# RAMPSXB.net
KiCad netlist of a schematic drawn in EAGLE
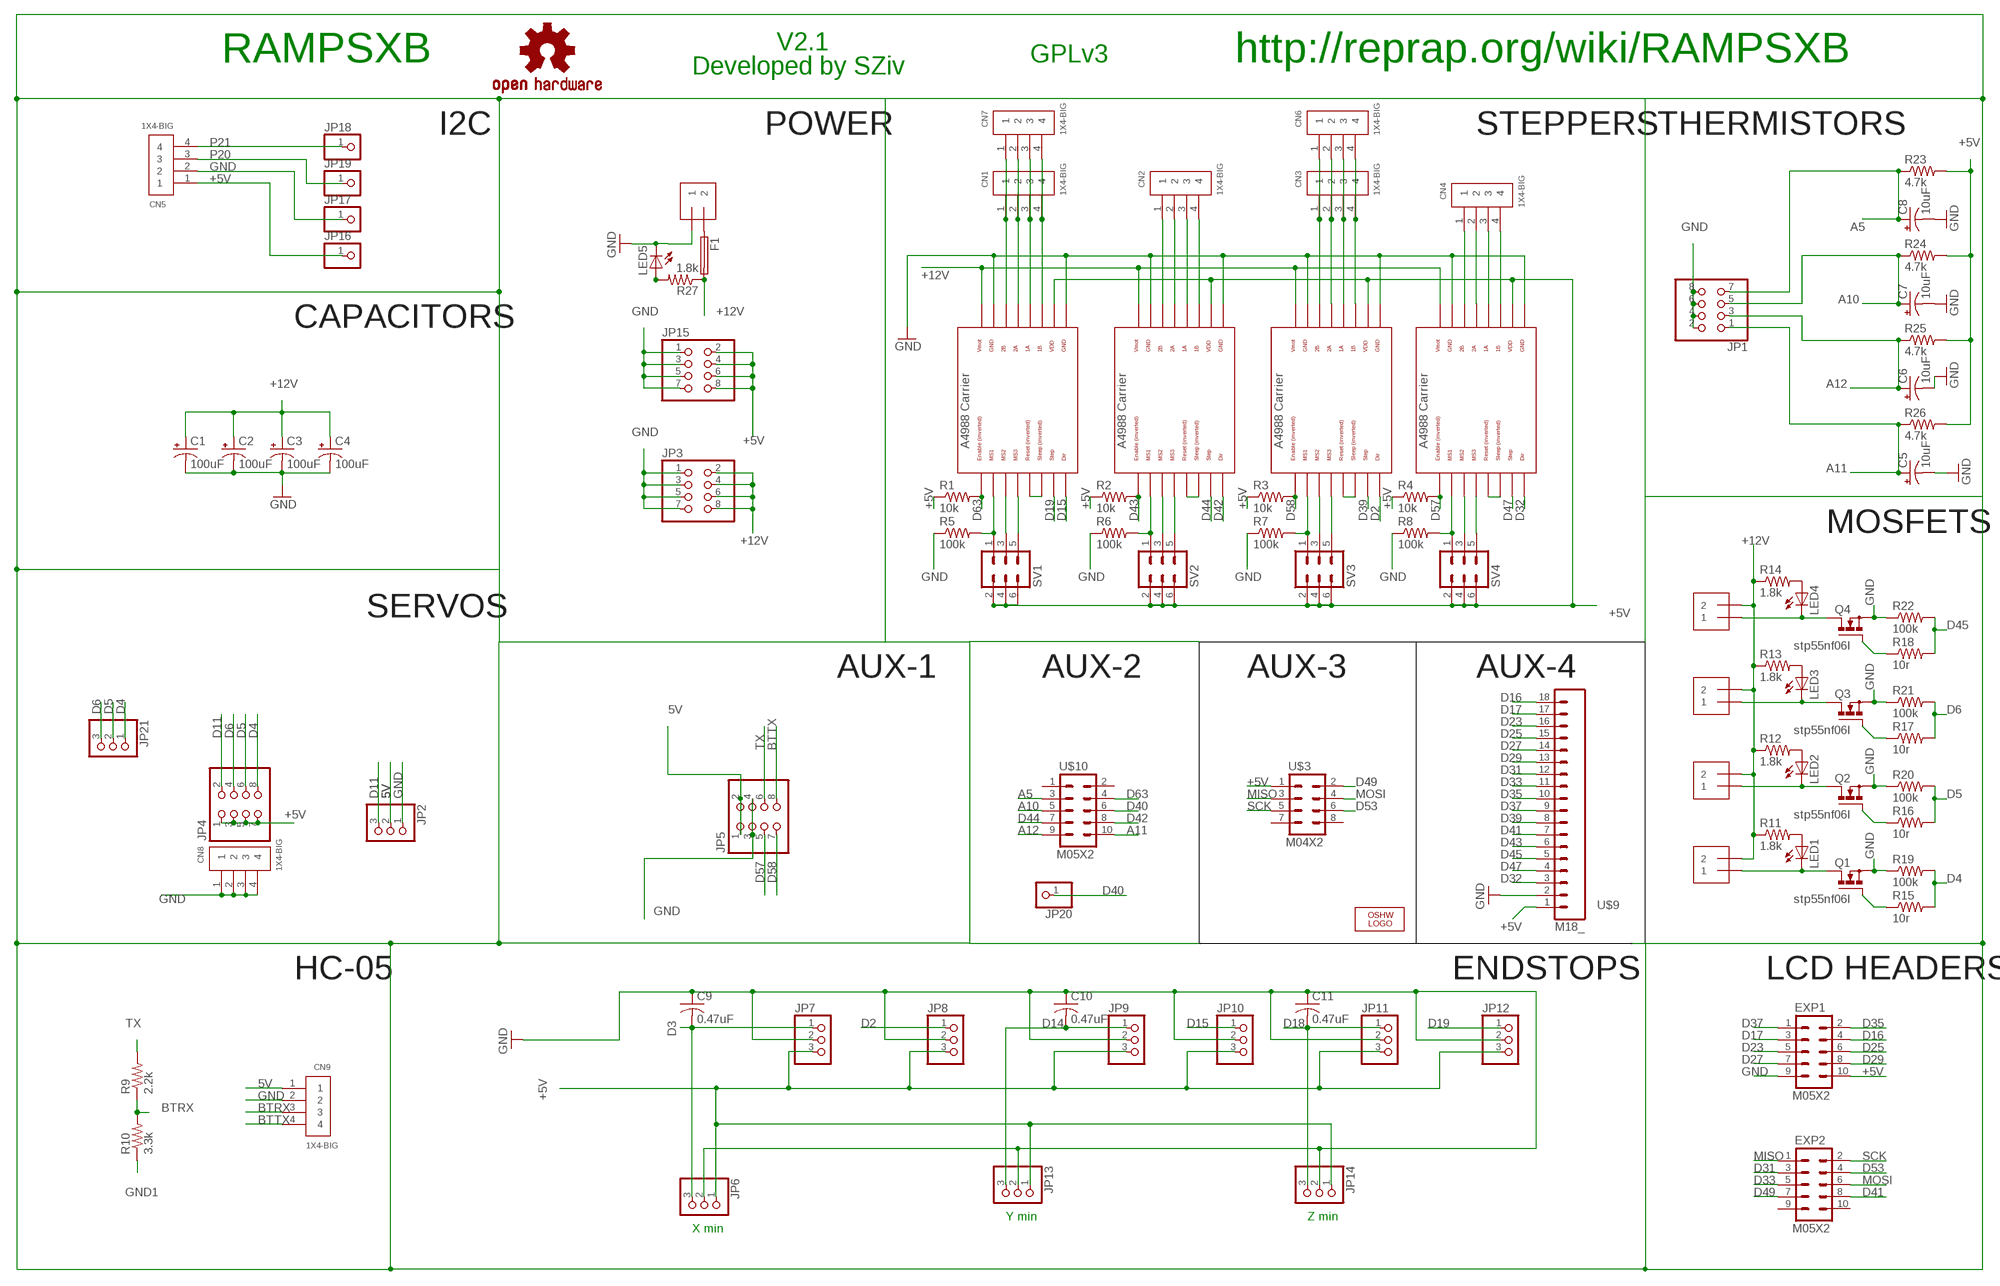
[diagram p0: schematic, sheet 1]

(export (version "E")
  (design (tool "Eeschema 10.0.6"))
  (components
    (comp (ref "C1")
      (value "100uF")
      (footprint "eagle-import:153CLV-0605")
      (libsource (lib "eagle-import") (part "CPOL-US153CLV-0605"))
    )
    (comp (ref "C2")
      (value "100uF")
      (footprint "eagle-import:153CLV-0605")
      (libsource (lib "eagle-import") (part "CPOL-US153CLV-0605"))
    )
    (comp (ref "C3")
      (value "100uF")
      (footprint "eagle-import:153CLV-0605")
      (libsource (lib "eagle-import") (part "CPOL-US153CLV-0605"))
    )
    (comp (ref "C4")
      (value "100uF")
      (footprint "eagle-import:153CLV-0605")
      (libsource (lib "eagle-import") (part "CPOL-US153CLV-0605"))
    )
    (comp (ref "C5")
      (value "10uF")
      (footprint "eagle-import:153CLV-0405")
      (libsource (lib "eagle-import") (part "CPOL-US153CLV-0405"))
    )
    (comp (ref "C6")
      (value "10uF")
      (footprint "eagle-import:153CLV-0405")
      (libsource (lib "eagle-import") (part "CPOL-US153CLV-0405"))
    )
    (comp (ref "C7")
      (value "10uF")
      (footprint "eagle-import:153CLV-0405")
      (libsource (lib "eagle-import") (part "CPOL-US153CLV-0405"))
    )
    (comp (ref "C8")
      (value "10uF")
      (footprint "eagle-import:153CLV-0405")
      (libsource (lib "eagle-import") (part "CPOL-US153CLV-0405"))
    )
    (comp (ref "C9")
      (value "0.47uF")
      (footprint "eagle-import:C0805")
      (libsource (lib "eagle-import") (part "C-USC0805"))
    )
    (comp (ref "C10")
      (value "0.47uF")
      (footprint "eagle-import:C0805")
      (libsource (lib "eagle-import") (part "C-USC0805"))
    )
    (comp (ref "C11")
      (value "0.47uF")
      (footprint "eagle-import:C0805")
      (libsource (lib "eagle-import") (part "C-USC0805"))
    )
    (comp (ref "CN1")
      (value "1X4-BIG")
      (footprint "eagle-import:1X04-BIG")
      (libsource (lib "eagle-import") (part "1X4-BIG"))
    )
    (comp (ref "CN2")
      (value "1X4-BIG")
      (footprint "eagle-import:1X04-BIG")
      (libsource (lib "eagle-import") (part "1X4-BIG"))
    )
    (comp (ref "CN3")
      (value "1X4-BIG")
      (footprint "eagle-import:1X04-BIG")
      (libsource (lib "eagle-import") (part "1X4-BIG"))
    )
    (comp (ref "CN4")
      (value "1X4-BIG")
      (footprint "eagle-import:1X04-BIG")
      (libsource (lib "eagle-import") (part "1X4-BIG"))
    )
    (comp (ref "CN5")
      (value "1X4-BIG")
      (footprint "eagle-import:1X04-BIG")
      (libsource (lib "eagle-import") (part "1X4-BIG"))
    )
    (comp (ref "CN6")
      (value "1X4-BIG")
      (footprint "eagle-import:1X04-BIG")
      (libsource (lib "eagle-import") (part "1X4-BIG"))
    )
    (comp (ref "CN7")
      (value "1X4-BIG")
      (footprint "eagle-import:1X04-BIG")
      (libsource (lib "eagle-import") (part "1X4-BIG"))
    )
    (comp (ref "CN8")
      (value "1X4-BIG")
      (footprint "eagle-import:1X04-BIG")
      (libsource (lib "eagle-import") (part "1X4-BIG"))
    )
    (comp (ref "CN9")
      (value "1X4-BIG")
      (footprint "eagle-import:1X04-BIG")
      (libsource (lib "eagle-import") (part "1X4-BIG"))
    )
    (comp (ref "EXP1")
      (value "M05X2")
      (footprint "eagle-import:2X5")
      (libsource (lib "eagle-import") (part "M05X2"))
    )
    (comp (ref "EXP2")
      (value "M05X2")
      (footprint "eagle-import:2X5")
      (libsource (lib "eagle-import") (part "M05X2"))
    )
    (comp (ref "F1")
      (value "PTCFUSE")
      (footprint "eagle-import:LITTLEFUSE")
      (libsource (lib "eagle-import") (part "PTCFUSE"))
    )
    (comp (ref "J1")
      (value "1X2-3.5MM")
      (footprint "eagle-import:1X2-3.5MM")
      (libsource (lib "eagle-import") (part "1X2-3.5MM"))
    )
    (comp (ref "J2")
      (value "1X2-3.5MM")
      (footprint "eagle-import:1X2-3.5MM")
      (libsource (lib "eagle-import") (part "1X2-3.5MM"))
    )
    (comp (ref "J3")
      (value "1X2-3.5MM")
      (footprint "eagle-import:1X2-3.5MM")
      (libsource (lib "eagle-import") (part "1X2-3.5MM"))
    )
    (comp (ref "J4")
      (value "1X2-3.5MM")
      (footprint "eagle-import:1X2-3.5MM")
      (libsource (lib "eagle-import") (part "1X2-3.5MM"))
    )
    (comp (ref "J5")
      (value "1X2-3.5MM")
      (footprint "eagle-import:1X2-3.5MM")
      (libsource (lib "eagle-import") (part "1X2-3.5MM"))
    )
    (comp (ref "JP1")
      (value "PINHD-2X4")
      (footprint "eagle-import:2X04")
      (libsource (lib "eagle-import") (part "PINHD-2X4"))
    )
    (comp (ref "JP2")
      (value "PINHD-1X3")
      (footprint "eagle-import:1X03")
      (libsource (lib "eagle-import") (part "PINHD-1X3"))
    )
    (comp (ref "JP3")
      (value "PINHD-2X4")
      (footprint "eagle-import:2X04")
      (libsource (lib "eagle-import") (part "PINHD-2X4"))
    )
    (comp (ref "JP4")
      (value "PINHD-2X4")
      (footprint "eagle-import:2X04")
      (libsource (lib "eagle-import") (part "PINHD-2X4"))
    )
    (comp (ref "JP5")
      (value "PINHD-2X4")
      (footprint "eagle-import:2X04")
      (libsource (lib "eagle-import") (part "PINHD-2X4"))
    )
    (comp (ref "JP6")
      (value "PINHD-1X3")
      (footprint "eagle-import:1X03")
      (libsource (lib "eagle-import") (part "PINHD-1X3"))
    )
    (comp (ref "JP7")
      (value "PINHD-1X3")
      (footprint "eagle-import:1X03")
      (libsource (lib "eagle-import") (part "PINHD-1X3"))
    )
    (comp (ref "JP8")
      (value "PINHD-1X3")
      (footprint "eagle-import:1X03")
      (libsource (lib "eagle-import") (part "PINHD-1X3"))
    )
    (comp (ref "JP9")
      (value "PINHD-1X3")
      (footprint "eagle-import:1X03")
      (libsource (lib "eagle-import") (part "PINHD-1X3"))
    )
    (comp (ref "JP10")
      (value "PINHD-1X3")
      (footprint "eagle-import:1X03")
      (libsource (lib "eagle-import") (part "PINHD-1X3"))
    )
    (comp (ref "JP11")
      (value "PINHD-1X3")
      (footprint "eagle-import:1X03")
      (libsource (lib "eagle-import") (part "PINHD-1X3"))
    )
    (comp (ref "JP12")
      (value "PINHD-1X3")
      (footprint "eagle-import:1X03")
      (libsource (lib "eagle-import") (part "PINHD-1X3"))
    )
    (comp (ref "JP13")
      (value "PINHD-1X3")
      (footprint "eagle-import:1X03")
      (libsource (lib "eagle-import") (part "PINHD-1X3"))
    )
    (comp (ref "JP14")
      (value "PINHD-1X3")
      (footprint "eagle-import:1X03")
      (libsource (lib "eagle-import") (part "PINHD-1X3"))
    )
    (comp (ref "JP15")
      (value "PINHD-2X4")
      (footprint "eagle-import:2X04")
      (libsource (lib "eagle-import") (part "PINHD-2X4"))
    )
    (comp (ref "JP16")
      (value "PINHD-1X1")
      (footprint "eagle-import:1X01")
      (libsource (lib "eagle-import") (part "PINHD-1X1"))
    )
    (comp (ref "JP17")
      (value "PINHD-1X1")
      (footprint "eagle-import:1X01")
      (libsource (lib "eagle-import") (part "PINHD-1X1"))
    )
    (comp (ref "JP18")
      (value "PINHD-1X1")
      (footprint "eagle-import:1X01")
      (libsource (lib "eagle-import") (part "PINHD-1X1"))
    )
    (comp (ref "JP19")
      (value "PINHD-1X1")
      (footprint "eagle-import:1X01")
      (libsource (lib "eagle-import") (part "PINHD-1X1"))
    )
    (comp (ref "JP20")
      (value "PINHD-1X1")
      (footprint "eagle-import:1X01")
      (libsource (lib "eagle-import") (part "PINHD-1X1"))
    )
    (comp (ref "JP21")
      (value "PINHD-1X3")
      (footprint "eagle-import:1X03")
      (libsource (lib "eagle-import") (part "PINHD-1X3"))
    )
    (comp (ref "LED1")
      (value "LEDCHIPLED_0805")
      (footprint "eagle-import:CHIPLED_0805")
      (libsource (lib "eagle-import") (part "LEDCHIPLED_0805"))
    )
    (comp (ref "LED2")
      (value "LEDCHIPLED_0805")
      (footprint "eagle-import:CHIPLED_0805")
      (libsource (lib "eagle-import") (part "LEDCHIPLED_0805"))
    )
    (comp (ref "LED3")
      (value "LEDCHIPLED_0805")
      (footprint "eagle-import:CHIPLED_0805")
      (libsource (lib "eagle-import") (part "LEDCHIPLED_0805"))
    )
    (comp (ref "LED4")
      (value "LEDCHIPLED_0805")
      (footprint "eagle-import:CHIPLED_0805")
      (libsource (lib "eagle-import") (part "LEDCHIPLED_0805"))
    )
    (comp (ref "LED5")
      (value "LEDCHIPLED_0805")
      (footprint "eagle-import:CHIPLED_0805")
      (libsource (lib "eagle-import") (part "LEDCHIPLED_0805"))
    )
    (comp (ref "LOGO1")
      (value "OSHW_LOGO_6MILX0100-NT")
      (footprint "eagle-import:OSHW_6X100_NOTEXT")
      (libsource (lib "eagle-import") (part "OSHW_LOGO_6MILX0100-NT"))
    )
    (comp (ref "LOGO2")
      (value "OSHW-LOGOL")
      (footprint "eagle-import:OSHW-LOGO-L")
      (libsource (lib "eagle-import") (part "OSHW-LOGOL"))
    )
    (comp (ref "Q1")
      (value "IRF512")
      (footprint "eagle-import:TO220BV")
      (libsource (lib "eagle-import") (part "IRF512"))
    )
    (comp (ref "Q2")
      (value "IRF512")
      (footprint "eagle-import:TO220BV")
      (libsource (lib "eagle-import") (part "IRF512"))
    )
    (comp (ref "Q3")
      (value "IRF512")
      (footprint "eagle-import:TO220BV")
      (libsource (lib "eagle-import") (part "IRF512"))
    )
    (comp (ref "Q4")
      (value "IRF512")
      (footprint "eagle-import:TO220BV")
      (libsource (lib "eagle-import") (part "IRF512"))
    )
    (comp (ref "R1")
      (value "10k")
      (footprint "eagle-import:M0805")
      (libsource (lib "eagle-import") (part "R-US_M0805"))
    )
    (comp (ref "R2")
      (value "10k")
      (footprint "eagle-import:M0805")
      (libsource (lib "eagle-import") (part "R-US_M0805"))
    )
    (comp (ref "R3")
      (value "10k")
      (footprint "eagle-import:M0805")
      (libsource (lib "eagle-import") (part "R-US_M0805"))
    )
    (comp (ref "R4")
      (value "10k")
      (footprint "eagle-import:M0805")
      (libsource (lib "eagle-import") (part "R-US_M0805"))
    )
    (comp (ref "R5")
      (value "100k")
      (footprint "eagle-import:M0805")
      (libsource (lib "eagle-import") (part "R-US_M0805"))
    )
    (comp (ref "R6")
      (value "100k")
      (footprint "eagle-import:M0805")
      (libsource (lib "eagle-import") (part "R-US_M0805"))
    )
    (comp (ref "R7")
      (value "100k")
      (footprint "eagle-import:M0805")
      (libsource (lib "eagle-import") (part "R-US_M0805"))
    )
    (comp (ref "R8")
      (value "100k")
      (footprint "eagle-import:M0805")
      (libsource (lib "eagle-import") (part "R-US_M0805"))
    )
    (comp (ref "R9")
      (value "2.2k")
      (footprint "eagle-import:M0805")
      (libsource (lib "eagle-import") (part "R-US_M0805"))
    )
    (comp (ref "R10")
      (value "3.3k")
      (footprint "eagle-import:M0805")
      (libsource (lib "eagle-import") (part "R-US_M0805"))
    )
    (comp (ref "R11")
      (value "1.8k")
      (footprint "eagle-import:M0805")
      (libsource (lib "eagle-import") (part "R-US_M0805"))
    )
    (comp (ref "R12")
      (value "1.8k")
      (footprint "eagle-import:M0805")
      (libsource (lib "eagle-import") (part "R-US_M0805"))
    )
    (comp (ref "R13")
      (value "1.8k")
      (footprint "eagle-import:M0805")
      (libsource (lib "eagle-import") (part "R-US_M0805"))
    )
    (comp (ref "R14")
      (value "1.8k")
      (footprint "eagle-import:M0805")
      (libsource (lib "eagle-import") (part "R-US_M0805"))
    )
    (comp (ref "R15")
      (value "10r")
      (footprint "eagle-import:M0805")
      (libsource (lib "eagle-import") (part "R-US_M0805"))
    )
    (comp (ref "R16")
      (value "10r")
      (footprint "eagle-import:M0805")
      (libsource (lib "eagle-import") (part "R-US_M0805"))
    )
    (comp (ref "R17")
      (value "10r")
      (footprint "eagle-import:M0805")
      (libsource (lib "eagle-import") (part "R-US_M0805"))
    )
    (comp (ref "R18")
      (value "10r")
      (footprint "eagle-import:M0805")
      (libsource (lib "eagle-import") (part "R-US_M0805"))
    )
    (comp (ref "R19")
      (value "100k")
      (footprint "eagle-import:M0805")
      (libsource (lib "eagle-import") (part "R-US_M0805"))
    )
    (comp (ref "R20")
      (value "100k")
      (footprint "eagle-import:M0805")
      (libsource (lib "eagle-import") (part "R-US_M0805"))
    )
    (comp (ref "R21")
      (value "100k")
      (footprint "eagle-import:M0805")
      (libsource (lib "eagle-import") (part "R-US_M0805"))
    )
    (comp (ref "R22")
      (value "100k")
      (footprint "eagle-import:M0805")
      (libsource (lib "eagle-import") (part "R-US_M0805"))
    )
    (comp (ref "R23")
      (value "4.7k")
      (footprint "eagle-import:R0805")
      (libsource (lib "eagle-import") (part "R-US_R0805"))
    )
    (comp (ref "R24")
      (value "4.7k")
      (footprint "eagle-import:R0805")
      (libsource (lib "eagle-import") (part "R-US_R0805"))
    )
    (comp (ref "R25")
      (value "4.7k")
      (footprint "eagle-import:R0805")
      (libsource (lib "eagle-import") (part "R-US_R0805"))
    )
    (comp (ref "R26")
      (value "4.7k")
      (footprint "eagle-import:R0805")
      (libsource (lib "eagle-import") (part "R-US_R0805"))
    )
    (comp (ref "R27")
      (value "1.8k")
      (footprint "eagle-import:M0805")
      (libsource (lib "eagle-import") (part "R-US_M0805"))
    )
    (comp (ref "SV1")
      (value "MA03-2")
      (footprint "eagle-import:MA03-2")
      (libsource (lib "eagle-import") (part "MA03-2"))
    )
    (comp (ref "SV2")
      (value "MA03-2")
      (footprint "eagle-import:MA03-2")
      (libsource (lib "eagle-import") (part "MA03-2"))
    )
    (comp (ref "SV3")
      (value "MA03-2")
      (footprint "eagle-import:MA03-2")
      (libsource (lib "eagle-import") (part "MA03-2"))
    )
    (comp (ref "SV4")
      (value "MA03-2")
      (footprint "eagle-import:MA03-2")
      (libsource (lib "eagle-import") (part "MA03-2"))
    )
    (comp (ref "U$1")
      (value "POLOLU_A4983CARRIER")
      (footprint "eagle-import:A4988BREAKOUT")
      (libsource (lib "eagle-import") (part "POLOLU_A4983CARRIER"))
    )
    (comp (ref "U$2")
      (value "POLOLU_A4983CARRIER")
      (footprint "eagle-import:A4988BREAKOUT")
      (libsource (lib "eagle-import") (part "POLOLU_A4983CARRIER"))
    )
    (comp (ref "U$3")
      (value "M04X2")
      (footprint "eagle-import:2X4")
      (libsource (lib "eagle-import") (part "M04X2"))
    )
    (comp (ref "U$4")
      (value "POLOLU_A4983CARRIER")
      (footprint "eagle-import:A4988BREAKOUT")
      (libsource (lib "eagle-import") (part "POLOLU_A4983CARRIER"))
    )
    (comp (ref "U$5")
      (value "POLOLU_A4983CARRIER")
      (footprint "eagle-import:A4988BREAKOUT")
      (libsource (lib "eagle-import") (part "POLOLU_A4983CARRIER"))
    )
    (comp (ref "U$9")
      (value "M18_")
      (footprint "eagle-import:1X18")
      (libsource (lib "eagle-import") (part "M18_"))
    )
    (comp (ref "U$10")
      (value "M05X2")
      (footprint "eagle-import:2X5")
      (libsource (lib "eagle-import") (part "M05X2"))
    )
  )
  (nets
    (net (code "1") (name "/+5V") (class "Default")
      (node (ref "CN5") (pin "1") (pinfunction "1_1") (pintype "bidirectional"))
      (node (ref "EXP1") (pin "10") (pinfunction "10_10") (pintype "passive"))
      (node (ref "JP10") (pin "3") (pinfunction "3_3") (pintype "passive"))
      (node (ref "JP11") (pin "3") (pinfunction "3_3") (pintype "passive"))
      (node (ref "JP12") (pin "3") (pinfunction "3_3") (pintype "passive"))
      (node (ref "JP13") (pin "1") (pinfunction "1_1") (pintype "passive"))
      (node (ref "JP14") (pin "1") (pinfunction "1_1") (pintype "passive"))
      (node (ref "JP15") (pin "2") (pinfunction "2_2") (pintype "passive"))
      (node (ref "JP15") (pin "4") (pinfunction "4_4") (pintype "passive"))
      (node (ref "JP15") (pin "6") (pinfunction "6_6") (pintype "passive"))
      (node (ref "JP15") (pin "8") (pinfunction "8_8") (pintype "passive"))
      (node (ref "JP16") (pin "1") (pinfunction "1_1") (pintype "passive"))
      (node (ref "JP4") (pin "1") (pinfunction "1_1") (pintype "passive"))
      (node (ref "JP4") (pin "3") (pinfunction "3_3") (pintype "passive"))
      (node (ref "JP4") (pin "5") (pinfunction "5_5") (pintype "passive"))
      (node (ref "JP4") (pin "7") (pinfunction "7_7") (pintype "passive"))
      (node (ref "JP6") (pin "1") (pinfunction "1_1") (pintype "passive"))
      (node (ref "JP7") (pin "3") (pinfunction "3_3") (pintype "passive"))
      (node (ref "JP8") (pin "3") (pinfunction "3_3") (pintype "passive"))
      (node (ref "JP9") (pin "3") (pinfunction "3_3") (pintype "passive"))
      (node (ref "R1") (pin "1") (pinfunction "1_1") (pintype "passive"))
      (node (ref "R2") (pin "1") (pinfunction "1_1") (pintype "passive"))
      (node (ref "R23") (pin "2") (pinfunction "2_2") (pintype "passive"))
      (node (ref "R24") (pin "2") (pinfunction "2_2") (pintype "passive"))
      (node (ref "R25") (pin "2") (pinfunction "2_2") (pintype "passive"))
      (node (ref "R26") (pin "2") (pinfunction "2_2") (pintype "passive"))
      (node (ref "R3") (pin "1") (pinfunction "1_1") (pintype "passive"))
      (node (ref "R4") (pin "1") (pinfunction "1_1") (pintype "passive"))
      (node (ref "SV1") (pin "2") (pinfunction "2_2") (pintype "passive"))
      (node (ref "SV1") (pin "4") (pinfunction "4_4") (pintype "passive"))
      (node (ref "SV1") (pin "6") (pinfunction "6_6") (pintype "passive"))
      (node (ref "SV2") (pin "2") (pinfunction "2_2") (pintype "passive"))
      (node (ref "SV2") (pin "4") (pinfunction "4_4") (pintype "passive"))
      (node (ref "SV2") (pin "6") (pinfunction "6_6") (pintype "passive"))
      (node (ref "SV3") (pin "2") (pinfunction "2_2") (pintype "passive"))
      (node (ref "SV3") (pin "4") (pinfunction "4_4") (pintype "passive"))
      (node (ref "SV3") (pin "6") (pinfunction "6_6") (pintype "passive"))
      (node (ref "SV4") (pin "2") (pinfunction "2_2") (pintype "passive"))
      (node (ref "SV4") (pin "4") (pinfunction "4_4") (pintype "passive"))
      (node (ref "SV4") (pin "6") (pinfunction "6_6") (pintype "passive"))
      (node (ref "U$1") (pin "VDD") (pinfunction "VDD_VDD") (pintype "power_in"))
      (node (ref "U$2") (pin "VDD") (pinfunction "VDD_VDD") (pintype "power_in"))
      (node (ref "U$3") (pin "1") (pinfunction "1_1") (pintype "passive"))
      (node (ref "U$4") (pin "VDD") (pinfunction "VDD_VDD") (pintype "power_in"))
      (node (ref "U$5") (pin "VDD") (pinfunction "VDD_VDD") (pintype "power_in"))
      (node (ref "U$9") (pin "1") (pinfunction "1_1") (pintype "passive"))
    )
    (net (code "2") (name "/+12V") (class "Default")
      (node (ref "C1") (pin "+") (pinfunction "+_+") (pintype "passive"))
      (node (ref "C2") (pin "+") (pinfunction "+_+") (pintype "passive"))
      (node (ref "C3") (pin "+") (pinfunction "+_+") (pintype "passive"))
      (node (ref "C4") (pin "+") (pinfunction "+_+") (pintype "passive"))
      (node (ref "F1") (pin "2") (pinfunction "2_2") (pintype "passive"))
      (node (ref "J2") (pin "2") (pinfunction "2_2") (pintype "passive"))
      (node (ref "J3") (pin "2") (pinfunction "2_2") (pintype "passive"))
      (node (ref "J4") (pin "2") (pinfunction "2_2") (pintype "passive"))
      (node (ref "J5") (pin "2") (pinfunction "2_2") (pintype "passive"))
      (node (ref "JP3") (pin "2") (pinfunction "2_2") (pintype "passive"))
      (node (ref "JP3") (pin "4") (pinfunction "4_4") (pintype "passive"))
      (node (ref "JP3") (pin "6") (pinfunction "6_6") (pintype "passive"))
      (node (ref "JP3") (pin "8") (pinfunction "8_8") (pintype "passive"))
      (node (ref "R11") (pin "1") (pinfunction "1_1") (pintype "passive"))
      (node (ref "R12") (pin "1") (pinfunction "1_1") (pintype "passive"))
      (node (ref "R13") (pin "1") (pinfunction "1_1") (pintype "passive"))
      (node (ref "R14") (pin "1") (pinfunction "1_1") (pintype "passive"))
      (node (ref "R27") (pin "1") (pinfunction "1_1") (pintype "passive"))
      (node (ref "U$1") (pin "VMOT") (pinfunction "VMOT_VMOT") (pintype "power_in"))
      (node (ref "U$2") (pin "VMOT") (pinfunction "VMOT_VMOT") (pintype "power_in"))
      (node (ref "U$4") (pin "VMOT") (pinfunction "VMOT_VMOT") (pintype "power_in"))
      (node (ref "U$5") (pin "VMOT") (pinfunction "VMOT_VMOT") (pintype "power_in"))
    )
    (net (code "3") (name "/5V") (class "Default")
      (node (ref "CN9") (pin "1") (pinfunction "1_1") (pintype "bidirectional"))
      (node (ref "JP2") (pin "2") (pinfunction "2_2") (pintype "passive"))
      (node (ref "JP5") (pin "1") (pinfunction "1_1") (pintype "passive"))
      (node (ref "JP5") (pin "2") (pinfunction "2_2") (pintype "passive"))
    )
    (net (code "4") (name "/A5") (class "Default")
      (node (ref "C8") (pin "+") (pinfunction "+_+") (pintype "passive"))
      (node (ref "JP1") (pin "7") (pinfunction "7_7") (pintype "passive"))
      (node (ref "R23") (pin "1") (pinfunction "1_1") (pintype "passive"))
      (node (ref "U$10") (pin "3") (pinfunction "3_3") (pintype "passive"))
    )
    (net (code "5") (name "/A10") (class "Default")
      (node (ref "C7") (pin "+") (pinfunction "+_+") (pintype "passive"))
      (node (ref "JP1") (pin "5") (pinfunction "5_5") (pintype "passive"))
      (node (ref "R24") (pin "1") (pinfunction "1_1") (pintype "passive"))
      (node (ref "U$10") (pin "5") (pinfunction "5_5") (pintype "passive"))
    )
    (net (code "6") (name "/A11") (class "Default")
      (node (ref "C5") (pin "+") (pinfunction "+_+") (pintype "passive"))
      (node (ref "JP1") (pin "1") (pinfunction "1_1") (pintype "passive"))
      (node (ref "R26") (pin "1") (pinfunction "1_1") (pintype "passive"))
      (node (ref "U$10") (pin "10") (pinfunction "10_10") (pintype "passive"))
    )
    (net (code "7") (name "/A12") (class "Default")
      (node (ref "C6") (pin "+") (pinfunction "+_+") (pintype "passive"))
      (node (ref "JP1") (pin "3") (pinfunction "3_3") (pintype "passive"))
      (node (ref "R25") (pin "1") (pinfunction "1_1") (pintype "passive"))
      (node (ref "U$10") (pin "9") (pinfunction "9_9") (pintype "passive"))
    )
    (net (code "8") (name "/BTRX") (class "Default")
      (node (ref "CN9") (pin "3") (pinfunction "3_3") (pintype "bidirectional"))
      (node (ref "R10") (pin "2") (pinfunction "2_2") (pintype "passive"))
      (node (ref "R9") (pin "1") (pinfunction "1_1") (pintype "passive"))
    )
    (net (code "9") (name "/BTTX") (class "Default")
      (node (ref "CN9") (pin "4") (pinfunction "4_4") (pintype "bidirectional"))
      (node (ref "JP5") (pin "8") (pinfunction "8_8") (pintype "passive"))
    )
    (net (code "10") (name "/D2") (class "Default")
      (node (ref "JP8") (pin "1") (pinfunction "1_1") (pintype "passive"))
      (node (ref "U$4") (pin "DIR") (pinfunction "DIR_DIR") (pintype "input"))
    )
    (net (code "11") (name "/D3") (class "Default")
      (node (ref "C9") (pin "2") (pinfunction "2_2") (pintype "passive"))
      (node (ref "JP6") (pin "3") (pinfunction "3_3") (pintype "passive"))
      (node (ref "JP7") (pin "1") (pinfunction "1_1") (pintype "passive"))
    )
    (net (code "12") (name "/D4") (class "Default")
      (node (ref "JP21") (pin "1") (pinfunction "1_1") (pintype "passive"))
      (node (ref "JP4") (pin "8") (pinfunction "8_8") (pintype "passive"))
      (node (ref "R15") (pin "2") (pinfunction "2_2") (pintype "passive"))
      (node (ref "R19") (pin "2") (pinfunction "2_2") (pintype "passive"))
    )
    (net (code "13") (name "/D5") (class "Default")
      (node (ref "JP21") (pin "2") (pinfunction "2_2") (pintype "passive"))
      (node (ref "JP4") (pin "6") (pinfunction "6_6") (pintype "passive"))
      (node (ref "R16") (pin "2") (pinfunction "2_2") (pintype "passive"))
      (node (ref "R20") (pin "2") (pinfunction "2_2") (pintype "passive"))
    )
    (net (code "14") (name "/D6") (class "Default")
      (node (ref "JP21") (pin "3") (pinfunction "3_3") (pintype "passive"))
      (node (ref "JP4") (pin "4") (pinfunction "4_4") (pintype "passive"))
      (node (ref "R17") (pin "2") (pinfunction "2_2") (pintype "passive"))
      (node (ref "R21") (pin "2") (pinfunction "2_2") (pintype "passive"))
    )
    (net (code "15") (name "/D11") (class "Default")
      (node (ref "JP2") (pin "3") (pinfunction "3_3") (pintype "passive"))
      (node (ref "JP4") (pin "2") (pinfunction "2_2") (pintype "passive"))
    )
    (net (code "16") (name "/D14") (class "Default")
      (node (ref "C10") (pin "2") (pinfunction "2_2") (pintype "passive"))
      (node (ref "JP13") (pin "3") (pinfunction "3_3") (pintype "passive"))
      (node (ref "JP9") (pin "1") (pinfunction "1_1") (pintype "passive"))
    )
    (net (code "17") (name "/D15") (class "Default")
      (node (ref "JP10") (pin "1") (pinfunction "1_1") (pintype "passive"))
      (node (ref "U$1") (pin "DIR") (pinfunction "DIR_DIR") (pintype "input"))
    )
    (net (code "18") (name "/D16") (class "Default")
      (node (ref "EXP1") (pin "4") (pinfunction "4_4") (pintype "passive"))
      (node (ref "U$9") (pin "18") (pinfunction "18_18") (pintype "passive"))
    )
    (net (code "19") (name "/D17") (class "Default")
      (node (ref "EXP1") (pin "3") (pinfunction "3_3") (pintype "passive"))
      (node (ref "U$9") (pin "17") (pinfunction "17_17") (pintype "passive"))
    )
    (net (code "20") (name "/D18") (class "Default")
      (node (ref "C11") (pin "2") (pinfunction "2_2") (pintype "passive"))
      (node (ref "JP11") (pin "1") (pinfunction "1_1") (pintype "passive"))
      (node (ref "JP14") (pin "3") (pinfunction "3_3") (pintype "passive"))
    )
    (net (code "21") (name "/D19") (class "Default")
      (node (ref "JP12") (pin "1") (pinfunction "1_1") (pintype "passive"))
      (node (ref "U$1") (pin "STEP") (pinfunction "STEP_STEP") (pintype "input"))
    )
    (net (code "22") (name "/D23") (class "Default")
      (node (ref "EXP1") (pin "5") (pinfunction "5_5") (pintype "passive"))
      (node (ref "U$9") (pin "16") (pinfunction "16_16") (pintype "passive"))
    )
    (net (code "23") (name "/D25") (class "Default")
      (node (ref "EXP1") (pin "6") (pinfunction "6_6") (pintype "passive"))
      (node (ref "U$9") (pin "15") (pinfunction "15_15") (pintype "passive"))
    )
    (net (code "24") (name "/D27") (class "Default")
      (node (ref "EXP1") (pin "7") (pinfunction "7_7") (pintype "passive"))
      (node (ref "U$9") (pin "14") (pinfunction "14_14") (pintype "passive"))
    )
    (net (code "25") (name "/D29") (class "Default")
      (node (ref "EXP1") (pin "8") (pinfunction "8_8") (pintype "passive"))
      (node (ref "U$9") (pin "13") (pinfunction "13_13") (pintype "passive"))
    )
    (net (code "26") (name "/D31") (class "Default")
      (node (ref "EXP2") (pin "3") (pinfunction "3_3") (pintype "passive"))
      (node (ref "U$9") (pin "12") (pinfunction "12_12") (pintype "passive"))
    )
    (net (code "27") (name "/D32") (class "Default")
      (node (ref "U$5") (pin "DIR") (pinfunction "DIR_DIR") (pintype "input"))
      (node (ref "U$9") (pin "3") (pinfunction "3_3") (pintype "passive"))
    )
    (net (code "28") (name "/D33") (class "Default")
      (node (ref "EXP2") (pin "5") (pinfunction "5_5") (pintype "passive"))
      (node (ref "U$9") (pin "11") (pinfunction "11_11") (pintype "passive"))
    )
    (net (code "29") (name "/D35") (class "Default")
      (node (ref "EXP1") (pin "2") (pinfunction "2_2") (pintype "passive"))
      (node (ref "U$9") (pin "10") (pinfunction "10_10") (pintype "passive"))
    )
    (net (code "30") (name "/D37") (class "Default")
      (node (ref "EXP1") (pin "1") (pinfunction "1_1") (pintype "passive"))
      (node (ref "U$9") (pin "9") (pinfunction "9_9") (pintype "passive"))
    )
    (net (code "31") (name "/D39") (class "Default")
      (node (ref "U$4") (pin "STEP") (pinfunction "STEP_STEP") (pintype "input"))
      (node (ref "U$9") (pin "8") (pinfunction "8_8") (pintype "passive"))
    )
    (net (code "32") (name "/D40") (class "Default")
      (node (ref "JP20") (pin "1") (pinfunction "1_1") (pintype "passive"))
      (node (ref "U$10") (pin "6") (pinfunction "6_6") (pintype "passive"))
    )
    (net (code "33") (name "/D41") (class "Default")
      (node (ref "EXP2") (pin "8") (pinfunction "8_8") (pintype "passive"))
      (node (ref "U$9") (pin "7") (pinfunction "7_7") (pintype "passive"))
    )
    (net (code "34") (name "/D42") (class "Default")
      (node (ref "U$10") (pin "8") (pinfunction "8_8") (pintype "passive"))
      (node (ref "U$2") (pin "DIR") (pinfunction "DIR_DIR") (pintype "input"))
    )
    (net (code "35") (name "/D43") (class "Default")
      (node (ref "R2") (pin "2") (pinfunction "2_2") (pintype "passive"))
      (node (ref "U$2") (pin "EN") (pinfunction "EN_EN") (pintype "input"))
      (node (ref "U$9") (pin "6") (pinfunction "6_6") (pintype "passive"))
    )
    (net (code "36") (name "/D44") (class "Default")
      (node (ref "U$10") (pin "7") (pinfunction "7_7") (pintype "passive"))
      (node (ref "U$2") (pin "STEP") (pinfunction "STEP_STEP") (pintype "input"))
    )
    (net (code "37") (name "/D45") (class "Default")
      (node (ref "R18") (pin "2") (pinfunction "2_2") (pintype "passive"))
      (node (ref "R22") (pin "2") (pinfunction "2_2") (pintype "passive"))
      (node (ref "U$9") (pin "5") (pinfunction "5_5") (pintype "passive"))
    )
    (net (code "38") (name "/D47") (class "Default")
      (node (ref "U$5") (pin "STEP") (pinfunction "STEP_STEP") (pintype "input"))
      (node (ref "U$9") (pin "4") (pinfunction "4_4") (pintype "passive"))
    )
    (net (code "39") (name "/D49") (class "Default")
      (node (ref "EXP2") (pin "7") (pinfunction "7_7") (pintype "passive"))
      (node (ref "U$3") (pin "2") (pinfunction "2_2") (pintype "passive"))
    )
    (net (code "40") (name "/D53") (class "Default")
      (node (ref "EXP2") (pin "4") (pinfunction "4_4") (pintype "passive"))
      (node (ref "U$3") (pin "6") (pinfunction "6_6") (pintype "passive"))
    )
    (net (code "41") (name "/D57") (class "Default")
      (node (ref "JP5") (pin "5") (pinfunction "5_5") (pintype "passive"))
      (node (ref "R4") (pin "2") (pinfunction "2_2") (pintype "passive"))
      (node (ref "U$5") (pin "EN") (pinfunction "EN_EN") (pintype "input"))
    )
    (net (code "42") (name "/D58") (class "Default")
      (node (ref "JP5") (pin "7") (pinfunction "7_7") (pintype "passive"))
      (node (ref "R3") (pin "2") (pinfunction "2_2") (pintype "passive"))
      (node (ref "U$4") (pin "EN") (pinfunction "EN_EN") (pintype "input"))
    )
    (net (code "43") (name "/D63") (class "Default")
      (node (ref "R1") (pin "2") (pinfunction "2_2") (pintype "passive"))
      (node (ref "U$1") (pin "EN") (pinfunction "EN_EN") (pintype "input"))
      (node (ref "U$10") (pin "4") (pinfunction "4_4") (pintype "passive"))
    )
    (net (code "44") (name "/GND1") (class "Default")
      (node (ref "R10") (pin "1") (pinfunction "1_1") (pintype "passive"))
    )
    (net (code "45") (name "/MISO") (class "Default")
      (node (ref "EXP2") (pin "1") (pinfunction "1_1") (pintype "passive"))
      (node (ref "U$3") (pin "3") (pinfunction "3_3") (pintype "passive"))
    )
    (net (code "46") (name "/MOSI") (class "Default")
      (node (ref "EXP2") (pin "6") (pinfunction "6_6") (pintype "passive"))
      (node (ref "U$3") (pin "4") (pinfunction "4_4") (pintype "passive"))
    )
    (net (code "47") (name "/P20") (class "Default")
      (node (ref "CN5") (pin "3") (pinfunction "3_3") (pintype "bidirectional"))
      (node (ref "JP19") (pin "1") (pinfunction "1_1") (pintype "passive"))
    )
    (net (code "48") (name "/P21") (class "Default")
      (node (ref "CN5") (pin "4") (pinfunction "4_4") (pintype "bidirectional"))
      (node (ref "JP18") (pin "1") (pinfunction "1_1") (pintype "passive"))
    )
    (net (code "49") (name "/SCK") (class "Default")
      (node (ref "EXP2") (pin "2") (pinfunction "2_2") (pintype "passive"))
      (node (ref "U$3") (pin "5") (pinfunction "5_5") (pintype "passive"))
    )
    (net (code "50") (name "/TX") (class "Default")
      (node (ref "JP5") (pin "6") (pinfunction "6_6") (pintype "passive"))
      (node (ref "R9") (pin "2") (pinfunction "2_2") (pintype "passive"))
    )
    (net (code "51") (name "GND") (class "Default")
      (node (ref "C1") (pin "-") (pinfunction "-_-") (pintype "passive"))
      (node (ref "C10") (pin "1") (pinfunction "1_1") (pintype "passive"))
      (node (ref "C11") (pin "1") (pinfunction "1_1") (pintype "passive"))
      (node (ref "C2") (pin "-") (pinfunction "-_-") (pintype "passive"))
      (node (ref "C3") (pin "-") (pinfunction "-_-") (pintype "passive"))
      (node (ref "C4") (pin "-") (pinfunction "-_-") (pintype "passive"))
      (node (ref "C5") (pin "-") (pinfunction "-_-") (pintype "passive"))
      (node (ref "C6") (pin "-") (pinfunction "-_-") (pintype "passive"))
      (node (ref "C7") (pin "-") (pinfunction "-_-") (pintype "passive"))
      (node (ref "C8") (pin "-") (pinfunction "-_-") (pintype "passive"))
      (node (ref "C9") (pin "1") (pinfunction "1_1") (pintype "passive"))
      (node (ref "CN5") (pin "2") (pinfunction "2_2") (pintype "bidirectional"))
      (node (ref "CN8") (pin "1") (pinfunction "1_1") (pintype "bidirectional"))
      (node (ref "CN8") (pin "2") (pinfunction "2_2") (pintype "bidirectional"))
      (node (ref "CN8") (pin "3") (pinfunction "3_3") (pintype "bidirectional"))
      (node (ref "CN8") (pin "4") (pinfunction "4_4") (pintype "bidirectional"))
      (node (ref "CN9") (pin "2") (pinfunction "2_2") (pintype "bidirectional"))
      (node (ref "EXP1") (pin "9") (pinfunction "9_9") (pintype "passive"))
      (node (ref "J1") (pin "1") (pinfunction "1_1") (pintype "passive"))
      (node (ref "JP1") (pin "2") (pinfunction "2_2") (pintype "passive"))
      (node (ref "JP1") (pin "4") (pinfunction "4_4") (pintype "passive"))
      (node (ref "JP1") (pin "6") (pinfunction "6_6") (pintype "passive"))
      (node (ref "JP1") (pin "8") (pinfunction "8_8") (pintype "passive"))
      (node (ref "JP10") (pin "2") (pinfunction "2_2") (pintype "passive"))
      (node (ref "JP11") (pin "2") (pinfunction "2_2") (pintype "passive"))
      (node (ref "JP12") (pin "2") (pinfunction "2_2") (pintype "passive"))
      (node (ref "JP13") (pin "2") (pinfunction "2_2") (pintype "passive"))
      (node (ref "JP14") (pin "2") (pinfunction "2_2") (pintype "passive"))
      (node (ref "JP15") (pin "1") (pinfunction "1_1") (pintype "passive"))
      (node (ref "JP15") (pin "3") (pinfunction "3_3") (pintype "passive"))
      (node (ref "JP15") (pin "5") (pinfunction "5_5") (pintype "passive"))
      (node (ref "JP15") (pin "7") (pinfunction "7_7") (pintype "passive"))
      (node (ref "JP17") (pin "1") (pinfunction "1_1") (pintype "passive"))
      (node (ref "JP2") (pin "1") (pinfunction "1_1") (pintype "passive"))
      (node (ref "JP3") (pin "1") (pinfunction "1_1") (pintype "passive"))
      (node (ref "JP3") (pin "3") (pinfunction "3_3") (pintype "passive"))
      (node (ref "JP3") (pin "5") (pinfunction "5_5") (pintype "passive"))
      (node (ref "JP3") (pin "7") (pinfunction "7_7") (pintype "passive"))
      (node (ref "JP5") (pin "3") (pinfunction "3_3") (pintype "passive"))
      (node (ref "JP5") (pin "4") (pinfunction "4_4") (pintype "passive"))
      (node (ref "JP6") (pin "2") (pinfunction "2_2") (pintype "passive"))
      (node (ref "JP7") (pin "2") (pinfunction "2_2") (pintype "passive"))
      (node (ref "JP8") (pin "2") (pinfunction "2_2") (pintype "passive"))
      (node (ref "JP9") (pin "2") (pinfunction "2_2") (pintype "passive"))
      (node (ref "LED5") (pin "C") (pinfunction "C_C") (pintype "passive"))
      (node (ref "Q1") (pin "S") (pinfunction "S_S") (pintype "passive"))
      (node (ref "Q2") (pin "S") (pinfunction "S_S") (pintype "passive"))
      (node (ref "Q3") (pin "S") (pinfunction "S_S") (pintype "passive"))
      (node (ref "Q4") (pin "S") (pinfunction "S_S") (pintype "passive"))
      (node (ref "R19") (pin "1") (pinfunction "1_1") (pintype "passive"))
      (node (ref "R20") (pin "1") (pinfunction "1_1") (pintype "passive"))
      (node (ref "R21") (pin "1") (pinfunction "1_1") (pintype "passive"))
      (node (ref "R22") (pin "1") (pinfunction "1_1") (pintype "passive"))
      (node (ref "R5") (pin "1") (pinfunction "1_1") (pintype "passive"))
      (node (ref "R6") (pin "1") (pinfunction "1_1") (pintype "passive"))
      (node (ref "R7") (pin "1") (pinfunction "1_1") (pintype "passive"))
      (node (ref "R8") (pin "1") (pinfunction "1_1") (pintype "passive"))
      (node (ref "U$1") (pin "GND") (pinfunction "GND_GND") (pintype "power_in"))
      (node (ref "U$1") (pin "GND@0") (pinfunction "GND_GND@0") (pintype "power_in"))
      (node (ref "U$2") (pin "GND") (pinfunction "GND_GND") (pintype "power_in"))
      (node (ref "U$2") (pin "GND@0") (pinfunction "GND_GND@0") (pintype "power_in"))
      (node (ref "U$4") (pin "GND") (pinfunction "GND_GND") (pintype "power_in"))
      (node (ref "U$4") (pin "GND@0") (pinfunction "GND_GND@0") (pintype "power_in"))
      (node (ref "U$5") (pin "GND") (pinfunction "GND_GND") (pintype "power_in"))
      (node (ref "U$5") (pin "GND@0") (pinfunction "GND_GND@0") (pintype "power_in"))
      (node (ref "U$9") (pin "2") (pinfunction "2_2") (pintype "passive"))
    )
    (net (code "52") (name "Net-(CN1-Pad1)") (class "Default")
      (node (ref "CN1") (pin "1") (pinfunction "1_1") (pintype "bidirectional"))
      (node (ref "CN7") (pin "1") (pinfunction "1_1") (pintype "bidirectional"))
      (node (ref "U$1") (pin "2B") (pinfunction "2B_2B") (pintype "output"))
    )
    (net (code "53") (name "Net-(CN1-Pad2)") (class "Default")
      (node (ref "CN1") (pin "2") (pinfunction "2_2") (pintype "bidirectional"))
      (node (ref "CN7") (pin "2") (pinfunction "2_2") (pintype "bidirectional"))
      (node (ref "U$1") (pin "2A") (pinfunction "2A_2A") (pintype "output"))
    )
    (net (code "54") (name "Net-(CN1-Pad3)") (class "Default")
      (node (ref "CN1") (pin "3") (pinfunction "3_3") (pintype "bidirectional"))
      (node (ref "CN7") (pin "3") (pinfunction "3_3") (pintype "bidirectional"))
      (node (ref "U$1") (pin "1A") (pinfunction "1A_1A") (pintype "output"))
    )
    (net (code "55") (name "Net-(CN1-Pad4)") (class "Default")
      (node (ref "CN1") (pin "4") (pinfunction "4_4") (pintype "bidirectional"))
      (node (ref "CN7") (pin "4") (pinfunction "4_4") (pintype "bidirectional"))
      (node (ref "U$1") (pin "1B") (pinfunction "1B_1B") (pintype "output"))
    )
    (net (code "56") (name "Net-(CN2-Pad1)") (class "Default")
      (node (ref "CN2") (pin "1") (pinfunction "1_1") (pintype "bidirectional"))
      (node (ref "U$2") (pin "2B") (pinfunction "2B_2B") (pintype "output"))
    )
    (net (code "57") (name "Net-(CN2-Pad2)") (class "Default")
      (node (ref "CN2") (pin "2") (pinfunction "2_2") (pintype "bidirectional"))
      (node (ref "U$2") (pin "2A") (pinfunction "2A_2A") (pintype "output"))
    )
    (net (code "58") (name "Net-(CN2-Pad3)") (class "Default")
      (node (ref "CN2") (pin "3") (pinfunction "3_3") (pintype "bidirectional"))
      (node (ref "U$2") (pin "1A") (pinfunction "1A_1A") (pintype "output"))
    )
    (net (code "59") (name "Net-(CN2-Pad4)") (class "Default")
      (node (ref "CN2") (pin "4") (pinfunction "4_4") (pintype "bidirectional"))
      (node (ref "U$2") (pin "1B") (pinfunction "1B_1B") (pintype "output"))
    )
    (net (code "60") (name "Net-(CN3-Pad1)") (class "Default")
      (node (ref "CN3") (pin "1") (pinfunction "1_1") (pintype "bidirectional"))
      (node (ref "CN6") (pin "1") (pinfunction "1_1") (pintype "bidirectional"))
      (node (ref "U$4") (pin "2B") (pinfunction "2B_2B") (pintype "output"))
    )
    (net (code "61") (name "Net-(CN3-Pad2)") (class "Default")
      (node (ref "CN3") (pin "2") (pinfunction "2_2") (pintype "bidirectional"))
      (node (ref "CN6") (pin "2") (pinfunction "2_2") (pintype "bidirectional"))
      (node (ref "U$4") (pin "2A") (pinfunction "2A_2A") (pintype "output"))
    )
    (net (code "62") (name "Net-(CN3-Pad3)") (class "Default")
      (node (ref "CN3") (pin "3") (pinfunction "3_3") (pintype "bidirectional"))
      (node (ref "CN6") (pin "3") (pinfunction "3_3") (pintype "bidirectional"))
      (node (ref "U$4") (pin "1A") (pinfunction "1A_1A") (pintype "output"))
    )
    (net (code "63") (name "Net-(CN3-Pad4)") (class "Default")
      (node (ref "CN3") (pin "4") (pinfunction "4_4") (pintype "bidirectional"))
      (node (ref "CN6") (pin "4") (pinfunction "4_4") (pintype "bidirectional"))
      (node (ref "U$4") (pin "1B") (pinfunction "1B_1B") (pintype "output"))
    )
    (net (code "64") (name "Net-(CN4-Pad1)") (class "Default")
      (node (ref "CN4") (pin "1") (pinfunction "1_1") (pintype "bidirectional"))
      (node (ref "U$5") (pin "2B") (pinfunction "2B_2B") (pintype "output"))
    )
    (net (code "65") (name "Net-(CN4-Pad2)") (class "Default")
      (node (ref "CN4") (pin "2") (pinfunction "2_2") (pintype "bidirectional"))
      (node (ref "U$5") (pin "2A") (pinfunction "2A_2A") (pintype "output"))
    )
    (net (code "66") (name "Net-(CN4-Pad3)") (class "Default")
      (node (ref "CN4") (pin "3") (pinfunction "3_3") (pintype "bidirectional"))
      (node (ref "U$5") (pin "1A") (pinfunction "1A_1A") (pintype "output"))
    )
    (net (code "67") (name "Net-(CN4-Pad4)") (class "Default")
      (node (ref "CN4") (pin "4") (pinfunction "4_4") (pintype "bidirectional"))
      (node (ref "U$5") (pin "1B") (pinfunction "1B_1B") (pintype "output"))
    )
    (net (code "68") (name "Net-(F1-Pad1)") (class "Default")
      (node (ref "F1") (pin "1") (pinfunction "1_1") (pintype "passive"))
      (node (ref "J1") (pin "2") (pinfunction "2_2") (pintype "passive"))
    )
    (net (code "69") (name "Net-(J2-Pad1)") (class "Default")
      (node (ref "J2") (pin "1") (pinfunction "1_1") (pintype "passive"))
      (node (ref "LED1") (pin "C") (pinfunction "C_C") (pintype "passive"))
      (node (ref "Q1") (pin "D") (pinfunction "D_D") (pintype "passive"))
    )
    (net (code "70") (name "Net-(J3-Pad1)") (class "Default")
      (node (ref "J3") (pin "1") (pinfunction "1_1") (pintype "passive"))
      (node (ref "LED2") (pin "C") (pinfunction "C_C") (pintype "passive"))
      (node (ref "Q2") (pin "D") (pinfunction "D_D") (pintype "passive"))
    )
    (net (code "71") (name "Net-(J4-Pad1)") (class "Default")
      (node (ref "J4") (pin "1") (pinfunction "1_1") (pintype "passive"))
      (node (ref "LED3") (pin "C") (pinfunction "C_C") (pintype "passive"))
      (node (ref "Q3") (pin "D") (pinfunction "D_D") (pintype "passive"))
    )
    (net (code "72") (name "Net-(J5-Pad1)") (class "Default")
      (node (ref "J5") (pin "1") (pinfunction "1_1") (pintype "passive"))
      (node (ref "LED4") (pin "C") (pinfunction "C_C") (pintype "passive"))
      (node (ref "Q4") (pin "D") (pinfunction "D_D") (pintype "passive"))
    )
    (net (code "73") (name "Net-(LED1-PadA)") (class "Default")
      (node (ref "LED1") (pin "A") (pinfunction "A_A") (pintype "passive"))
      (node (ref "R11") (pin "2") (pinfunction "2_2") (pintype "passive"))
    )
    (net (code "74") (name "Net-(LED2-PadA)") (class "Default")
      (node (ref "LED2") (pin "A") (pinfunction "A_A") (pintype "passive"))
      (node (ref "R12") (pin "2") (pinfunction "2_2") (pintype "passive"))
    )
    (net (code "75") (name "Net-(LED3-PadA)") (class "Default")
      (node (ref "LED3") (pin "A") (pinfunction "A_A") (pintype "passive"))
      (node (ref "R13") (pin "2") (pinfunction "2_2") (pintype "passive"))
    )
    (net (code "76") (name "Net-(LED4-PadA)") (class "Default")
      (node (ref "LED4") (pin "A") (pinfunction "A_A") (pintype "passive"))
      (node (ref "R14") (pin "2") (pinfunction "2_2") (pintype "passive"))
    )
    (net (code "77") (name "Net-(LED5-PadA)") (class "Default")
      (node (ref "LED5") (pin "A") (pinfunction "A_A") (pintype "passive"))
      (node (ref "R27") (pin "2") (pinfunction "2_2") (pintype "passive"))
    )
    (net (code "78") (name "Net-(Q1-PadG)") (class "Default")
      (node (ref "Q1") (pin "G") (pinfunction "G_G") (pintype "passive"))
      (node (ref "R15") (pin "1") (pinfunction "1_1") (pintype "passive"))
    )
    (net (code "79") (name "Net-(Q2-PadG)") (class "Default")
      (node (ref "Q2") (pin "G") (pinfunction "G_G") (pintype "passive"))
      (node (ref "R16") (pin "1") (pinfunction "1_1") (pintype "passive"))
    )
    (net (code "80") (name "Net-(Q3-PadG)") (class "Default")
      (node (ref "Q3") (pin "G") (pinfunction "G_G") (pintype "passive"))
      (node (ref "R17") (pin "1") (pinfunction "1_1") (pintype "passive"))
    )
    (net (code "81") (name "Net-(Q4-PadG)") (class "Default")
      (node (ref "Q4") (pin "G") (pinfunction "G_G") (pintype "passive"))
      (node (ref "R18") (pin "1") (pinfunction "1_1") (pintype "passive"))
    )
    (net (code "82") (name "Net-(R5-Pad2)") (class "Default")
      (node (ref "R5") (pin "2") (pinfunction "2_2") (pintype "passive"))
      (node (ref "SV1") (pin "1") (pinfunction "1_1") (pintype "passive"))
      (node (ref "U$1") (pin "MS1") (pinfunction "MS1_MS1") (pintype "input"))
    )
    (net (code "83") (name "Net-(R6-Pad2)") (class "Default")
      (node (ref "R6") (pin "2") (pinfunction "2_2") (pintype "passive"))
      (node (ref "SV2") (pin "1") (pinfunction "1_1") (pintype "passive"))
      (node (ref "U$2") (pin "MS1") (pinfunction "MS1_MS1") (pintype "input"))
    )
    (net (code "84") (name "Net-(R7-Pad2)") (class "Default")
      (node (ref "R7") (pin "2") (pinfunction "2_2") (pintype "passive"))
      (node (ref "SV3") (pin "1") (pinfunction "1_1") (pintype "passive"))
      (node (ref "U$4") (pin "MS1") (pinfunction "MS1_MS1") (pintype "input"))
    )
    (net (code "85") (name "Net-(R8-Pad2)") (class "Default")
      (node (ref "R8") (pin "2") (pinfunction "2_2") (pintype "passive"))
      (node (ref "SV4") (pin "1") (pinfunction "1_1") (pintype "passive"))
      (node (ref "U$5") (pin "MS1") (pinfunction "MS1_MS1") (pintype "input"))
    )
    (net (code "86") (name "Net-(SV1-Pad3)") (class "Default")
      (node (ref "SV1") (pin "3") (pinfunction "3_3") (pintype "passive"))
      (node (ref "U$1") (pin "MS2") (pinfunction "MS2_MS2") (pintype "input"))
    )
    (net (code "87") (name "Net-(SV1-Pad5)") (class "Default")
      (node (ref "SV1") (pin "5") (pinfunction "5_5") (pintype "passive"))
      (node (ref "U$1") (pin "MS3") (pinfunction "MS3_MS3") (pintype "input"))
    )
    (net (code "88") (name "Net-(SV2-Pad3)") (class "Default")
      (node (ref "SV2") (pin "3") (pinfunction "3_3") (pintype "passive"))
      (node (ref "U$2") (pin "MS2") (pinfunction "MS2_MS2") (pintype "input"))
    )
    (net (code "89") (name "Net-(SV2-Pad5)") (class "Default")
      (node (ref "SV2") (pin "5") (pinfunction "5_5") (pintype "passive"))
      (node (ref "U$2") (pin "MS3") (pinfunction "MS3_MS3") (pintype "input"))
    )
    (net (code "90") (name "Net-(SV3-Pad3)") (class "Default")
      (node (ref "SV3") (pin "3") (pinfunction "3_3") (pintype "passive"))
      (node (ref "U$4") (pin "MS2") (pinfunction "MS2_MS2") (pintype "input"))
    )
    (net (code "91") (name "Net-(SV3-Pad5)") (class "Default")
      (node (ref "SV3") (pin "5") (pinfunction "5_5") (pintype "passive"))
      (node (ref "U$4") (pin "MS3") (pinfunction "MS3_MS3") (pintype "input"))
    )
    (net (code "92") (name "Net-(SV4-Pad3)") (class "Default")
      (node (ref "SV4") (pin "3") (pinfunction "3_3") (pintype "passive"))
      (node (ref "U$5") (pin "MS2") (pinfunction "MS2_MS2") (pintype "input"))
    )
    (net (code "93") (name "Net-(SV4-Pad5)") (class "Default")
      (node (ref "SV4") (pin "5") (pinfunction "5_5") (pintype "passive"))
      (node (ref "U$5") (pin "MS3") (pinfunction "MS3_MS3") (pintype "input"))
    )
    (net (code "94") (name "Net-(U$1-SLEEP)") (class "Default")
      (node (ref "U$1") (pin "RST") (pinfunction "RST_RST") (pintype "input"))
      (node (ref "U$1") (pin "SLP") (pinfunction "SLEEP_SLP") (pintype "input"))
    )
    (net (code "95") (name "Net-(U$2-SLEEP)") (class "Default")
      (node (ref "U$2") (pin "RST") (pinfunction "RST_RST") (pintype "input"))
      (node (ref "U$2") (pin "SLP") (pinfunction "SLEEP_SLP") (pintype "input"))
    )
    (net (code "96") (name "Net-(U$4-SLEEP)") (class "Default")
      (node (ref "U$4") (pin "RST") (pinfunction "RST_RST") (pintype "input"))
      (node (ref "U$4") (pin "SLP") (pinfunction "SLEEP_SLP") (pintype "input"))
    )
    (net (code "97") (name "Net-(U$5-SLEEP)") (class "Default")
      (node (ref "U$5") (pin "RST") (pinfunction "RST_RST") (pintype "input"))
      (node (ref "U$5") (pin "SLP") (pinfunction "SLEEP_SLP") (pintype "input"))
    )
    (net (code "98") (name "unconnected-(EXP2-Pad9)") (class "Default")
      (node (ref "EXP2") (pin "9") (pinfunction "9_9") (pintype "passive"))
    )
    (net (code "99") (name "unconnected-(EXP2-Pad10)") (class "Default")
      (node (ref "EXP2") (pin "10") (pinfunction "10_10") (pintype "passive"))
    )
    (net (code "100") (name "unconnected-(U$3-Pad7)") (class "Default")
      (node (ref "U$3") (pin "7") (pinfunction "7_7") (pintype "passive"))
    )
    (net (code "101") (name "unconnected-(U$3-Pad8)") (class "Default")
      (node (ref "U$3") (pin "8") (pinfunction "8_8") (pintype "passive"))
    )
    (net (code "102") (name "unconnected-(U$10-Pad1)") (class "Default")
      (node (ref "U$10") (pin "1") (pinfunction "1_1") (pintype "passive"))
    )
    (net (code "103") (name "unconnected-(U$10-Pad2)") (class "Default")
      (node (ref "U$10") (pin "2") (pinfunction "2_2") (pintype "passive"))
    )
  )
)
